# MOTHER_BOARD_SCHEMATIC.net
KiCad netlist of a schematic drawn in EasyEDA
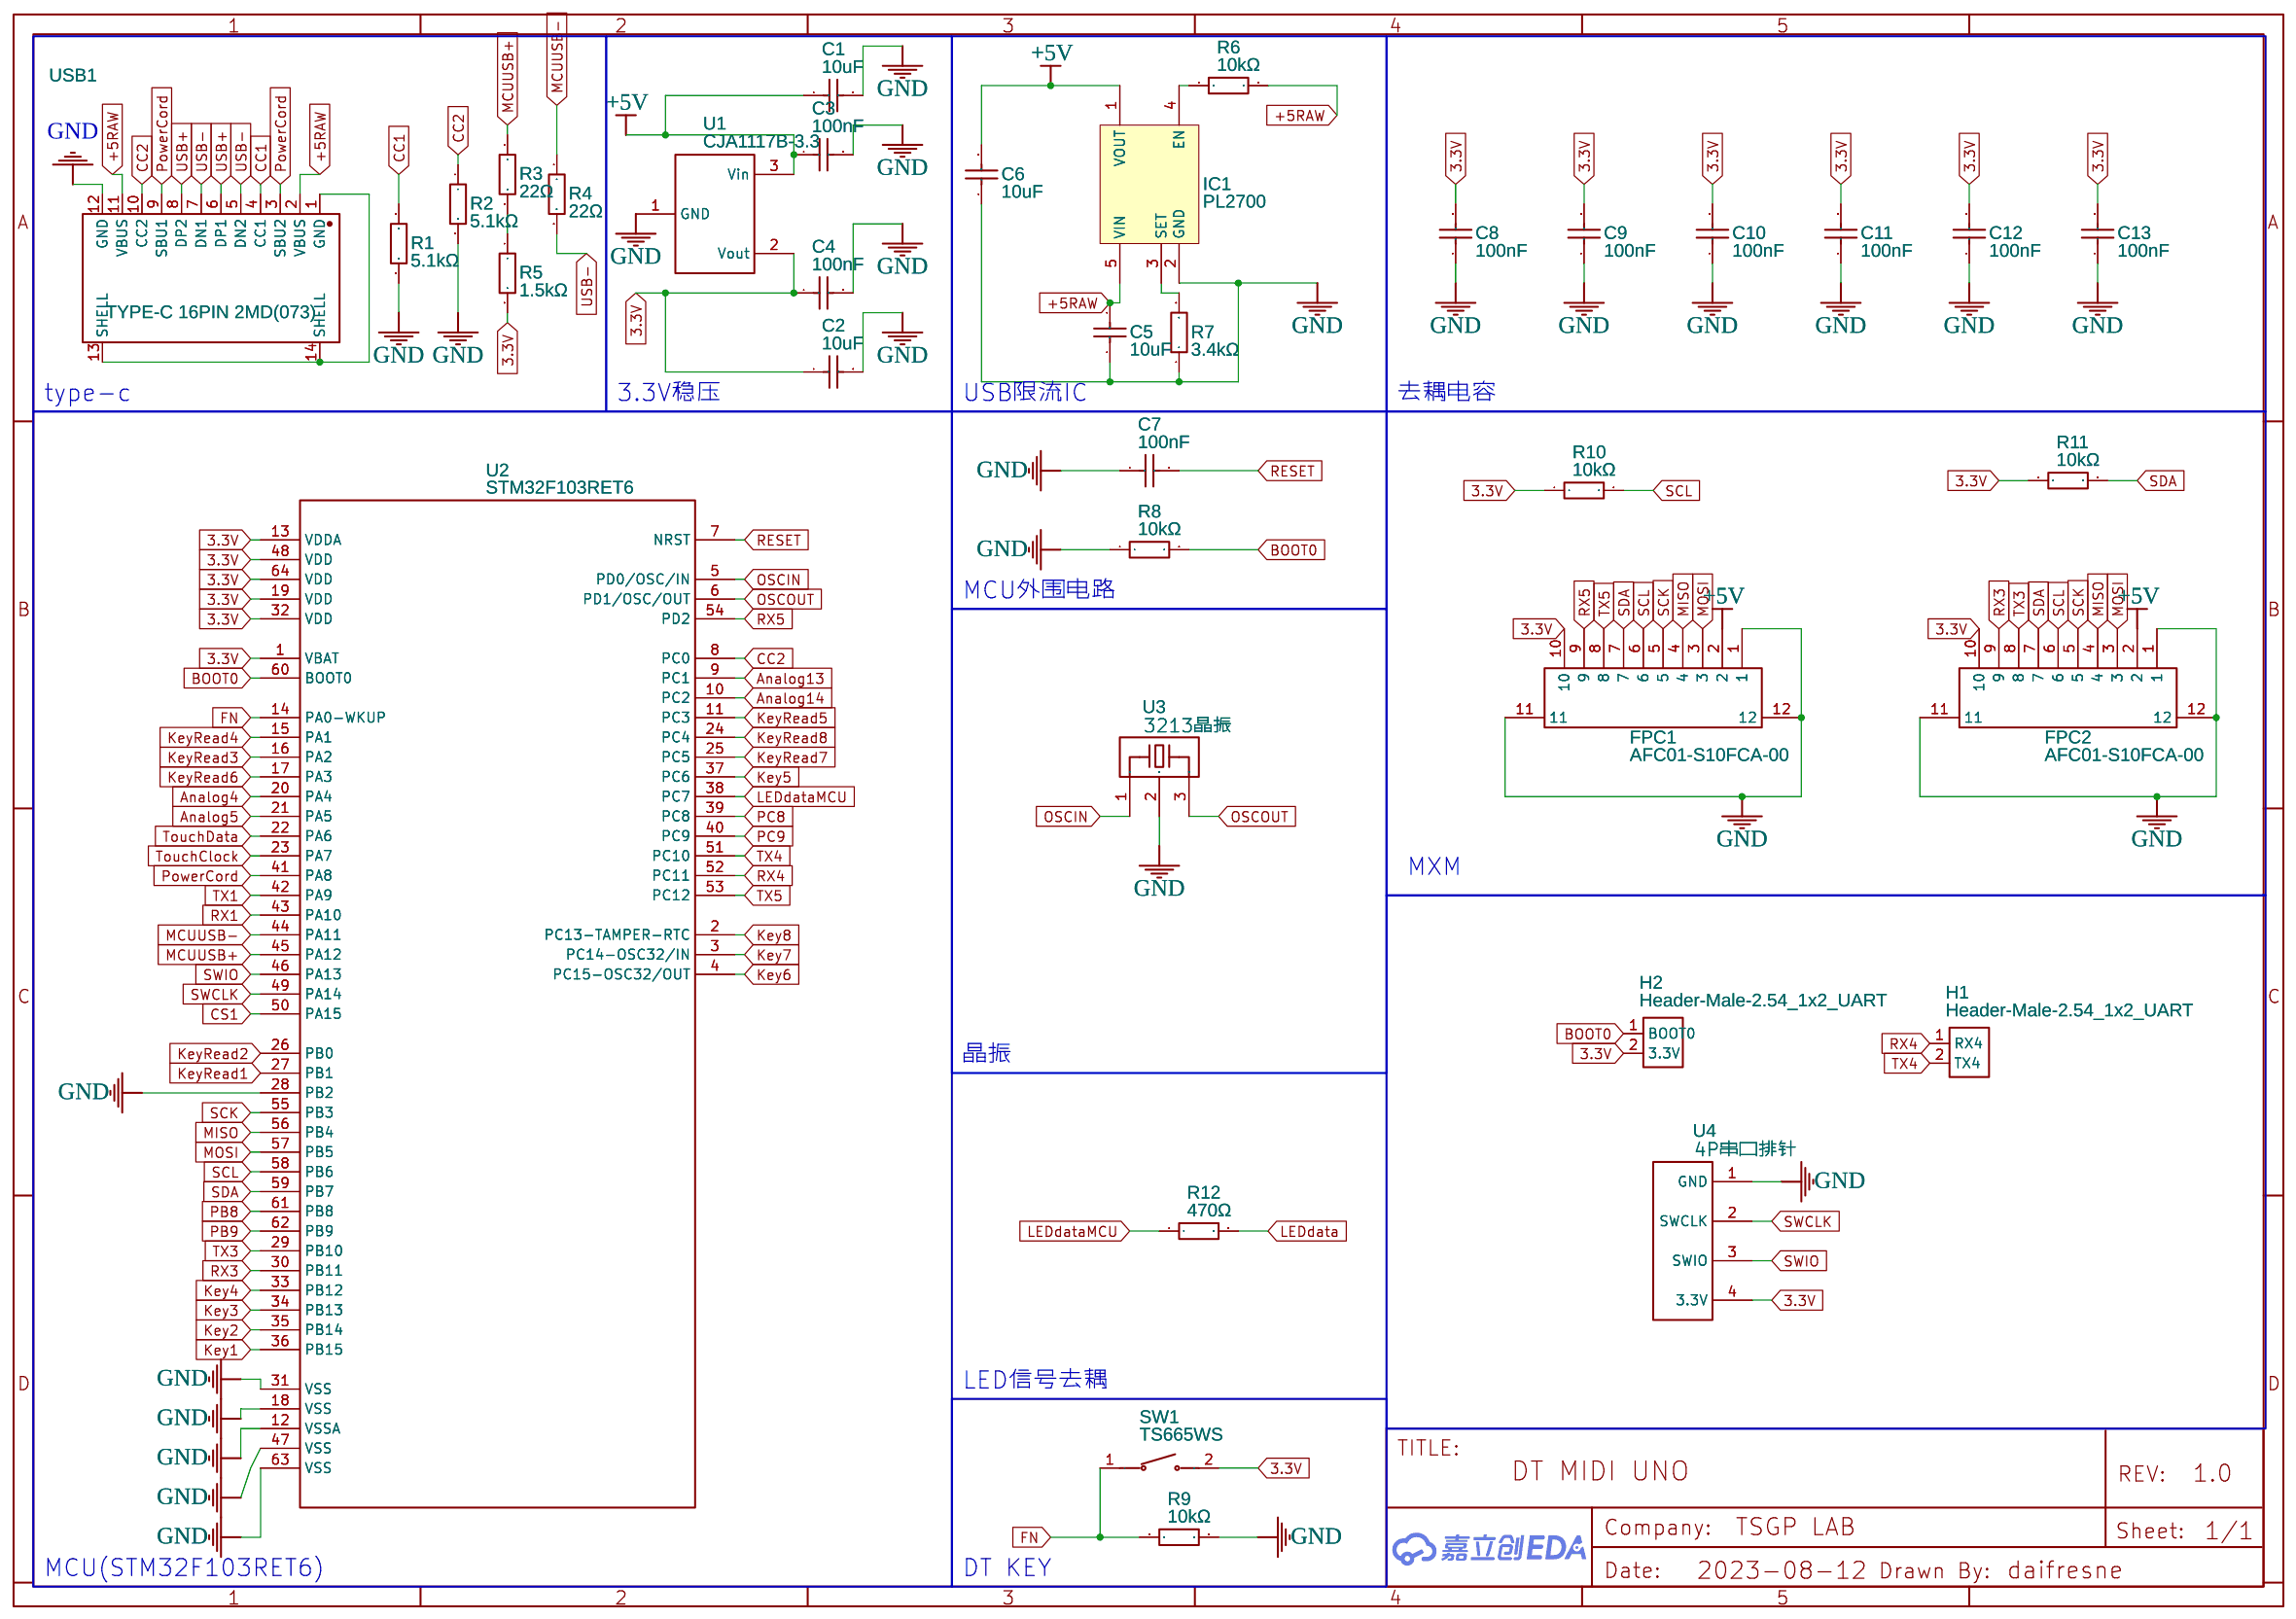
[diagram p0: schematic sheet]

(export (version "E")
  (design (tool "Eeschema 10.0.6"))
  (components
    (comp (ref "C1")
      (value "10uF")
      (fields (field (name "Manufacturer") "SAMSUNG(三星)"))
      (libsource (lib "") (part "CL21A106KAYNNNE"))
    )
    (comp (ref "C2")
      (value "10uF")
      (fields (field (name "Manufacturer") "SAMSUNG(三星)"))
      (libsource (lib "") (part "CL21A106KAYNNNE"))
    )
    (comp (ref "C3")
      (value "100nF")
      (fields (field (name "Manufacturer") "YAGEO(国巨)"))
      (libsource (lib "") (part "CC0603KRX7R8BB104_1"))
    )
    (comp (ref "C4")
      (value "100nF")
      (fields (field (name "Manufacturer") "YAGEO(国巨)"))
      (libsource (lib "") (part "CC0603KRX7R8BB104_1"))
    )
    (comp (ref "C5")
      (value "10uF")
      (fields (field (name "Manufacturer") "SAMSUNG(三星)"))
      (libsource (lib "") (part "CL21A106KAYNNNE_1"))
    )
    (comp (ref "C6")
      (value "10uF")
      (fields (field (name "Manufacturer") "SAMSUNG(三星)"))
      (libsource (lib "") (part "CL21A106KAYNNNE_1"))
    )
    (comp (ref "C7")
      (value "100nF")
      (fields (field (name "Manufacturer") "YAGEO(国巨)"))
      (libsource (lib "") (part "CC0603KRX7R8BB104_1"))
    )
    (comp (ref "C8")
      (value "100nF")
      (fields (field (name "Manufacturer") "YAGEO(国巨)"))
      (libsource (lib "") (part "CC0603KRX7R8BB104"))
    )
    (comp (ref "C9")
      (value "100nF")
      (fields (field (name "Manufacturer") "YAGEO(国巨)"))
      (libsource (lib "") (part "CC0603KRX7R8BB104"))
    )
    (comp (ref "C10")
      (value "100nF")
      (fields (field (name "Manufacturer") "YAGEO(国巨)"))
      (libsource (lib "") (part "CC0603KRX7R8BB104"))
    )
    (comp (ref "C11")
      (value "100nF")
      (fields (field (name "Manufacturer") "YAGEO(国巨)"))
      (libsource (lib "") (part "CC0603KRX7R8BB104"))
    )
    (comp (ref "C12")
      (value "100nF")
      (fields (field (name "Manufacturer") "YAGEO(国巨)"))
      (libsource (lib "") (part "CC0603KRX7R8BB104"))
    )
    (comp (ref "C13")
      (value "100nF")
      (fields (field (name "Manufacturer") "YAGEO(国巨)"))
      (libsource (lib "") (part "CC0603KRX7R8BB104"))
    )
    (comp (ref "FPC1")
      (value "AFC01-S10FCA-00")
      (fields (field (name "Manufacturer") "JS(钜硕电子)"))
      (libsource (lib "") (part "AFC01-S10FCA-00"))
    )
    (comp (ref "FPC2")
      (value "AFC01-S10FCA-00")
      (fields (field (name "Manufacturer") "JS(钜硕电子)"))
      (libsource (lib "") (part "AFC01-S10FCA-00"))
    )
    (comp (ref "H1")
      (value "Header-Male-2.54_1x2_UART")
      (fields (field (name "Manufacturer Part") "826629-2") (field (name "Manufacturer") "TE Connectivity"))
      (libsource (lib "") (part "Header-Male-2.54_1x2_UART_1"))
    )
    (comp (ref "H2")
      (value "Header-Male-2.54_1x2_UART")
      (fields (field (name "Manufacturer Part") "826629-2") (field (name "Manufacturer") "TE Connectivity"))
      (libsource (lib "") (part "Header-Male-2.54_1x2_UART"))
    )
    (comp (ref "IC1") (value "PL2700") (libsource (lib "") (part "PL2700")))
    (comp (ref "R1")
      (value "5.1kΩ")
      (fields (field (name "Manufacturer") "YAGEO(国巨)"))
      (libsource (lib "") (part "RT0603BRD075K1L_1"))
    )
    (comp (ref "R2")
      (value "5.1kΩ")
      (fields (field (name "Manufacturer") "YAGEO(国巨)"))
      (libsource (lib "") (part "RT0603BRD075K1L"))
    )
    (comp (ref "R3")
      (value "22Ω")
      (fields (field (name "Manufacturer") "UNI-ROYAL(厚声)"))
      (libsource (lib "") (part "0603WAF220JT5E"))
    )
    (comp (ref "R4")
      (value "22Ω")
      (fields (field (name "Manufacturer") "UNI-ROYAL(厚声)"))
      (libsource (lib "") (part "0603WAF220JT5E"))
    )
    (comp (ref "R5")
      (value "1.5kΩ")
      (fields (field (name "Manufacturer") "UNI-ROYAL(厚声)"))
      (libsource (lib "") (part "0603WAF1501T5E"))
    )
    (comp (ref "R6")
      (value "10kΩ")
      (fields (field (name "Manufacturer") "YAGEO(国巨)"))
      (libsource (lib "") (part "RT0805BRD0710KL"))
    )
    (comp (ref "R7")
      (value "3.4kΩ")
      (fields (field (name "Manufacturer") "UNI-ROYAL(厚声)"))
      (libsource (lib "") (part "0603WAF3401T5E"))
    )
    (comp (ref "R8")
      (value "10kΩ")
      (fields (field (name "Manufacturer") "YAGEO(国巨)"))
      (libsource (lib "") (part "RT0805BRD0710KL"))
    )
    (comp (ref "R9")
      (value "10kΩ")
      (fields (field (name "Manufacturer") "YAGEO(国巨)"))
      (libsource (lib "") (part "RT0805BRD0710KL"))
    )
    (comp (ref "R10")
      (value "10kΩ")
      (fields (field (name "Manufacturer") "YAGEO(国巨)"))
      (libsource (lib "") (part "RT0805BRD0710KL"))
    )
    (comp (ref "R11")
      (value "10kΩ")
      (fields (field (name "Manufacturer") "YAGEO(国巨)"))
      (libsource (lib "") (part "RT0805BRD0710KL"))
    )
    (comp (ref "R12")
      (value "470Ω")
      (fields (field (name "Manufacturer") "UNI-ROYAL(厚声)"))
      (libsource (lib "") (part "0603WAF4700T5E"))
    )
    (comp (ref "SW1")
      (value "TS665WS")
      (fields (field (name "Manufacturer") "SHOU HAN(首韩)"))
      (libsource (lib "") (part "TS665WS"))
    )
    (comp (ref "U1")
      (value "CJA1117B-3.3")
      (fields (field (name "Manufacturer") "CJ(江苏长电/长晶)"))
      (libsource (lib "") (part "CJA1117B-3.3"))
    )
    (comp (ref "U2")
      (value "STM32F103RET6")
      (fields (field (name "Manufacturer") "ST(意法半导体)"))
      (libsource (lib "") (part "STM32F103RET6"))
    )
    (comp (ref "U3") (value "3213晶振") (libsource (lib "") (part "3213晶振")))
    (comp (ref "U4") (value "4P串口排针") (libsource (lib "") (part "4P串口排针")))
    (comp (ref "USB1")
      (value "TYPE-C 16PIN 2MD(073)")
      (fields (field (name "Manufacturer") "SHOU HAN(首韩)"))
      (libsource (lib "") (part "TYPE-C 16PIN 2MD(073)"))
    )
  )
  (nets
    (net (code "1") (name "+5RAW") (class "Default")
      (node (ref "C5") (pin "2") (pinfunction "2_2") (pintype "input"))
      (node (ref "IC1") (pin "5") (pinfunction "VIN_5") (pintype "unspecified"))
      (node (ref "R6") (pin "2") (pinfunction "2_2") (pintype "input"))
      (node (ref "USB1") (pin "11") (pinfunction "VBUS_11") (pintype "unspecified"))
      (node (ref "USB1") (pin "2") (pinfunction "VBUS_2") (pintype "unspecified"))
    )
    (net (code "2") (name "+5V") (class "Default")
      (node (ref "C1") (pin "1") (pinfunction "1_1") (pintype "input"))
      (node (ref "C3") (pin "1") (pinfunction "1_1") (pintype "input"))
      (node (ref "C6") (pin "2") (pinfunction "2_2") (pintype "input"))
      (node (ref "FPC1") (pin "2") (pinfunction "2_2") (pintype "unspecified"))
      (node (ref "FPC2") (pin "2") (pinfunction "2_2") (pintype "unspecified"))
      (node (ref "IC1") (pin "1") (pinfunction "VOUT_1") (pintype "unspecified"))
      (node (ref "U1") (pin "3") (pinfunction "Vin_3") (pintype "unspecified"))
    )
    (net (code "3") (name "3.3V") (class "Default")
      (node (ref "C10") (pin "2") (pinfunction "2_2") (pintype "input"))
      (node (ref "C11") (pin "2") (pinfunction "2_2") (pintype "input"))
      (node (ref "C12") (pin "2") (pinfunction "2_2") (pintype "input"))
      (node (ref "C13") (pin "2") (pinfunction "2_2") (pintype "input"))
      (node (ref "C2") (pin "1") (pinfunction "1_1") (pintype "input"))
      (node (ref "C4") (pin "1") (pinfunction "1_1") (pintype "input"))
      (node (ref "C8") (pin "2") (pinfunction "2_2") (pintype "input"))
      (node (ref "C9") (pin "2") (pinfunction "2_2") (pintype "input"))
      (node (ref "FPC1") (pin "10") (pinfunction "10_10") (pintype "unspecified"))
      (node (ref "FPC2") (pin "10") (pinfunction "10_10") (pintype "unspecified"))
      (node (ref "H2") (pin "2") (pinfunction "3.3V_2") (pintype "unspecified"))
      (node (ref "R10") (pin "1") (pinfunction "1_1") (pintype "input"))
      (node (ref "R11") (pin "1") (pinfunction "1_1") (pintype "input"))
      (node (ref "R5") (pin "2") (pinfunction "2_2") (pintype "input"))
      (node (ref "SW1") (pin "2") (pinfunction "B_2") (pintype "unspecified"))
      (node (ref "U1") (pin "2") (pinfunction "Vout_2") (pintype "unspecified"))
      (node (ref "U2") (pin "1") (pinfunction "VBAT_1") (pintype "input"))
      (node (ref "U2") (pin "13") (pinfunction "VDDA_13") (pintype "passive"))
      (node (ref "U2") (pin "19") (pinfunction "VDD_19") (pintype "passive"))
      (node (ref "U2") (pin "32") (pinfunction "VDD_32") (pintype "passive"))
      (node (ref "U2") (pin "48") (pinfunction "VDD_48") (pintype "passive"))
      (node (ref "U2") (pin "64") (pinfunction "VDD_64") (pintype "passive"))
      (node (ref "U4") (pin "4") (pinfunction "3.3V_4") (pintype "unspecified"))
    )
    (net (code "4") (name "Analog4") (class "Default")
      (node (ref "U2") (pin "20") (pinfunction "PA4_20") (pintype "unspecified"))
    )
    (net (code "5") (name "Analog5") (class "Default")
      (node (ref "U2") (pin "21") (pinfunction "PA5_21") (pintype "unspecified"))
    )
    (net (code "6") (name "Analog13") (class "Default")
      (node (ref "U2") (pin "9") (pinfunction "PC1_9") (pintype "unspecified"))
    )
    (net (code "7") (name "Analog14") (class "Default")
      (node (ref "U2") (pin "10") (pinfunction "PC2_10") (pintype "unspecified"))
    )
    (net (code "8") (name "BOOT0") (class "Default")
      (node (ref "H2") (pin "1") (pinfunction "BOOT0_1") (pintype "unspecified"))
      (node (ref "R8") (pin "2") (pinfunction "2_2") (pintype "input"))
      (node (ref "U2") (pin "60") (pinfunction "BOOT0_60") (pintype "unspecified"))
    )
    (net (code "9") (name "CC1") (class "Default")
      (node (ref "R1") (pin "2") (pinfunction "2_2") (pintype "input"))
      (node (ref "USB1") (pin "4") (pinfunction "CC1_4") (pintype "unspecified"))
    )
    (net (code "10") (name "CC2") (class "Default")
      (node (ref "R2") (pin "1") (pinfunction "1_1") (pintype "input"))
      (node (ref "U2") (pin "8") (pinfunction "PC0_8") (pintype "unspecified"))
      (node (ref "USB1") (pin "10") (pinfunction "CC2_10") (pintype "unspecified"))
    )
    (net (code "11") (name "CS1") (class "Default")
      (node (ref "U2") (pin "50") (pinfunction "PA15_50") (pintype "unspecified"))
    )
    (net (code "12") (name "FN") (class "Default")
      (node (ref "R9") (pin "1") (pinfunction "1_1") (pintype "input"))
      (node (ref "SW1") (pin "1") (pinfunction "A_1") (pintype "unspecified"))
      (node (ref "U2") (pin "14") (pinfunction "PA0-WKUP_14") (pintype "unspecified"))
    )
    (net (code "13") (name "GND") (class "Default")
      (node (ref "C1") (pin "2") (pinfunction "2_2") (pintype "input"))
      (node (ref "C10") (pin "1") (pinfunction "1_1") (pintype "input"))
      (node (ref "C11") (pin "1") (pinfunction "1_1") (pintype "input"))
      (node (ref "C12") (pin "1") (pinfunction "1_1") (pintype "input"))
      (node (ref "C13") (pin "1") (pinfunction "1_1") (pintype "input"))
      (node (ref "C2") (pin "2") (pinfunction "2_2") (pintype "input"))
      (node (ref "C3") (pin "2") (pinfunction "2_2") (pintype "input"))
      (node (ref "C4") (pin "2") (pinfunction "2_2") (pintype "input"))
      (node (ref "C5") (pin "1") (pinfunction "1_1") (pintype "input"))
      (node (ref "C6") (pin "1") (pinfunction "1_1") (pintype "input"))
      (node (ref "C7") (pin "1") (pinfunction "1_1") (pintype "input"))
      (node (ref "C8") (pin "1") (pinfunction "1_1") (pintype "input"))
      (node (ref "C9") (pin "1") (pinfunction "1_1") (pintype "input"))
      (node (ref "FPC1") (pin "1") (pinfunction "1_1") (pintype "unspecified"))
      (node (ref "FPC1") (pin "11") (pinfunction "11_11") (pintype "unspecified"))
      (node (ref "FPC1") (pin "12") (pinfunction "12_12") (pintype "unspecified"))
      (node (ref "FPC2") (pin "1") (pinfunction "1_1") (pintype "unspecified"))
      (node (ref "FPC2") (pin "11") (pinfunction "11_11") (pintype "unspecified"))
      (node (ref "FPC2") (pin "12") (pinfunction "12_12") (pintype "unspecified"))
      (node (ref "IC1") (pin "2") (pinfunction "GND_2") (pintype "unspecified"))
      (node (ref "R1") (pin "1") (pinfunction "1_1") (pintype "input"))
      (node (ref "R2") (pin "2") (pinfunction "2_2") (pintype "input"))
      (node (ref "R7") (pin "1") (pinfunction "1_1") (pintype "input"))
      (node (ref "R8") (pin "1") (pinfunction "1_1") (pintype "input"))
      (node (ref "R9") (pin "2") (pinfunction "2_2") (pintype "input"))
      (node (ref "U1") (pin "1") (pinfunction "GND_1") (pintype "unspecified"))
      (node (ref "U2") (pin "12") (pinfunction "VSSA_12") (pintype "unspecified"))
      (node (ref "U2") (pin "18") (pinfunction "VSS_18") (pintype "unspecified"))
      (node (ref "U2") (pin "28") (pinfunction "PB2_28") (pintype "unspecified"))
      (node (ref "U2") (pin "31") (pinfunction "VSS_31") (pintype "unspecified"))
      (node (ref "U2") (pin "47") (pinfunction "VSS_47") (pintype "unspecified"))
      (node (ref "U2") (pin "63") (pinfunction "VSS_63") (pintype "unspecified"))
      (node (ref "U3") (pin "2") (pinfunction "2_2") (pintype "unspecified"))
      (node (ref "U4") (pin "1") (pinfunction "GND_1") (pintype "unspecified"))
      (node (ref "USB1") (pin "12") (pinfunction "GND_12") (pintype "unspecified"))
    )
    (net (code "14") (name "Key1") (class "Default")
      (node (ref "U2") (pin "36") (pinfunction "PB15_36") (pintype "unspecified"))
    )
    (net (code "15") (name "Key2") (class "Default")
      (node (ref "U2") (pin "35") (pinfunction "PB14_35") (pintype "unspecified"))
    )
    (net (code "16") (name "Key3") (class "Default")
      (node (ref "U2") (pin "34") (pinfunction "PB13_34") (pintype "unspecified"))
    )
    (net (code "17") (name "Key4") (class "Default")
      (node (ref "U2") (pin "33") (pinfunction "PB12_33") (pintype "unspecified"))
    )
    (net (code "18") (name "Key5") (class "Default")
      (node (ref "U2") (pin "37") (pinfunction "PC6_37") (pintype "unspecified"))
    )
    (net (code "19") (name "Key6") (class "Default")
      (node (ref "U2") (pin "4") (pinfunction "PC15-OSC32/OUT_4") (pintype "output"))
    )
    (net (code "20") (name "Key7") (class "Default")
      (node (ref "U2") (pin "3") (pinfunction "PC14-OSC32/IN_3") (pintype "input"))
    )
    (net (code "21") (name "Key8") (class "Default")
      (node (ref "U2") (pin "2") (pinfunction "PC13-TAMPER-RTC_2") (pintype "input"))
    )
    (net (code "22") (name "KeyRead1") (class "Default")
      (node (ref "U2") (pin "27") (pinfunction "PB1_27") (pintype "unspecified"))
    )
    (net (code "23") (name "KeyRead2") (class "Default")
      (node (ref "U2") (pin "26") (pinfunction "PB0_26") (pintype "unspecified"))
    )
    (net (code "24") (name "KeyRead3") (class "Default")
      (node (ref "U2") (pin "16") (pinfunction "PA2_16") (pintype "unspecified"))
    )
    (net (code "25") (name "KeyRead4") (class "Default")
      (node (ref "U2") (pin "15") (pinfunction "PA1_15") (pintype "unspecified"))
    )
    (net (code "26") (name "KeyRead5") (class "Default")
      (node (ref "U2") (pin "11") (pinfunction "PC3_11") (pintype "unspecified"))
    )
    (net (code "27") (name "KeyRead6") (class "Default")
      (node (ref "U2") (pin "17") (pinfunction "PA3_17") (pintype "unspecified"))
    )
    (net (code "28") (name "KeyRead7") (class "Default")
      (node (ref "U2") (pin "25") (pinfunction "PC5_25") (pintype "unspecified"))
    )
    (net (code "29") (name "KeyRead8") (class "Default")
      (node (ref "U2") (pin "24") (pinfunction "PC4_24") (pintype "unspecified"))
    )
    (net (code "30") (name "LEDdata") (class "Default")
      (node (ref "R12") (pin "2") (pinfunction "2_2") (pintype "input"))
    )
    (net (code "31") (name "LEDdataMCU") (class "Default")
      (node (ref "R12") (pin "1") (pinfunction "1_1") (pintype "input"))
      (node (ref "U2") (pin "38") (pinfunction "PC7_38") (pintype "unspecified"))
    )
    (net (code "32") (name "MCUUSB+") (class "Default")
      (node (ref "R3") (pin "1") (pinfunction "1_1") (pintype "input"))
      (node (ref "U2") (pin "45") (pinfunction "PA12_45") (pintype "unspecified"))
    )
    (net (code "33") (name "MCUUSB-") (class "Default")
      (node (ref "R4") (pin "1") (pinfunction "1_1") (pintype "input"))
      (node (ref "U2") (pin "44") (pinfunction "PA11_44") (pintype "unspecified"))
    )
    (net (code "34") (name "MISO") (class "Default")
      (node (ref "FPC1") (pin "4") (pinfunction "4_4") (pintype "unspecified"))
      (node (ref "FPC2") (pin "4") (pinfunction "4_4") (pintype "unspecified"))
      (node (ref "U2") (pin "56") (pinfunction "PB4_56") (pintype "unspecified"))
    )
    (net (code "35") (name "MOSI") (class "Default")
      (node (ref "FPC1") (pin "3") (pinfunction "3_3") (pintype "unspecified"))
      (node (ref "FPC2") (pin "3") (pinfunction "3_3") (pintype "unspecified"))
      (node (ref "U2") (pin "57") (pinfunction "PB5_57") (pintype "unspecified"))
    )
    (net (code "36") (name "Net-(IC1-EN)") (class "Default")
      (node (ref "IC1") (pin "4") (pinfunction "EN_4") (pintype "unspecified"))
      (node (ref "R6") (pin "1") (pinfunction "1_1") (pintype "input"))
    )
    (net (code "37") (name "Net-(IC1-SET)") (class "Default")
      (node (ref "IC1") (pin "3") (pinfunction "SET_3") (pintype "unspecified"))
      (node (ref "R7") (pin "2") (pinfunction "2_2") (pintype "input"))
    )
    (net (code "38") (name "Net-(R3-Pad2)") (class "Default")
      (node (ref "R3") (pin "2") (pinfunction "2_2") (pintype "input"))
      (node (ref "R5") (pin "1") (pinfunction "1_1") (pintype "input"))
    )
    (net (code "39") (name "Net-(USB1-GND-Pad1)") (class "Default")
      (node (ref "USB1") (pin "1") (pinfunction "GND_1") (pintype "unspecified"))
      (node (ref "USB1") (pin "13") (pinfunction "SHELL_13") (pintype "unspecified"))
      (node (ref "USB1") (pin "14") (pinfunction "SHELL_14") (pintype "unspecified"))
    )
    (net (code "40") (name "OSCIN") (class "Default")
      (node (ref "U2") (pin "5") (pinfunction "PD0/OSC/IN_5") (pintype "input"))
      (node (ref "U3") (pin "1") (pinfunction "1_1") (pintype "unspecified"))
    )
    (net (code "41") (name "OSCOUT") (class "Default")
      (node (ref "U2") (pin "6") (pinfunction "PD1/OSC/OUT_6") (pintype "output"))
      (node (ref "U3") (pin "3") (pinfunction "3_3") (pintype "unspecified"))
    )
    (net (code "42") (name "PB8") (class "Default")
      (node (ref "U2") (pin "61") (pinfunction "PB8_61") (pintype "unspecified"))
    )
    (net (code "43") (name "PB9") (class "Default")
      (node (ref "U2") (pin "62") (pinfunction "PB9_62") (pintype "unspecified"))
    )
    (net (code "44") (name "PC8") (class "Default")
      (node (ref "U2") (pin "39") (pinfunction "PC8_39") (pintype "unspecified"))
    )
    (net (code "45") (name "PC9") (class "Default")
      (node (ref "U2") (pin "40") (pinfunction "PC9_40") (pintype "unspecified"))
    )
    (net (code "46") (name "PowerCord") (class "Default")
      (node (ref "U2") (pin "41") (pinfunction "PA8_41") (pintype "unspecified"))
      (node (ref "USB1") (pin "3") (pinfunction "SBU2_3") (pintype "unspecified"))
      (node (ref "USB1") (pin "9") (pinfunction "SBU1_9") (pintype "unspecified"))
    )
    (net (code "47") (name "RESET") (class "Default")
      (node (ref "C7") (pin "2") (pinfunction "2_2") (pintype "input"))
      (node (ref "U2") (pin "7") (pinfunction "NRST_7") (pintype "output"))
    )
    (net (code "48") (name "RX1") (class "Default")
      (node (ref "U2") (pin "43") (pinfunction "PA10_43") (pintype "unspecified"))
    )
    (net (code "49") (name "RX3") (class "Default")
      (node (ref "FPC2") (pin "9") (pinfunction "9_9") (pintype "unspecified"))
      (node (ref "U2") (pin "30") (pinfunction "PB11_30") (pintype "unspecified"))
    )
    (net (code "50") (name "RX4") (class "Default")
      (node (ref "H1") (pin "1") (pinfunction "RX4_1") (pintype "unspecified"))
      (node (ref "U2") (pin "52") (pinfunction "PC11_52") (pintype "unspecified"))
    )
    (net (code "51") (name "RX5") (class "Default")
      (node (ref "FPC1") (pin "9") (pinfunction "9_9") (pintype "unspecified"))
      (node (ref "U2") (pin "54") (pinfunction "PD2_54") (pintype "unspecified"))
    )
    (net (code "52") (name "SCK") (class "Default")
      (node (ref "FPC1") (pin "5") (pinfunction "5_5") (pintype "unspecified"))
      (node (ref "FPC2") (pin "5") (pinfunction "5_5") (pintype "unspecified"))
      (node (ref "U2") (pin "55") (pinfunction "PB3_55") (pintype "unspecified"))
    )
    (net (code "53") (name "SCL") (class "Default")
      (node (ref "FPC1") (pin "6") (pinfunction "6_6") (pintype "unspecified"))
      (node (ref "FPC2") (pin "6") (pinfunction "6_6") (pintype "unspecified"))
      (node (ref "R10") (pin "2") (pinfunction "2_2") (pintype "input"))
      (node (ref "U2") (pin "58") (pinfunction "PB6_58") (pintype "unspecified"))
    )
    (net (code "54") (name "SDA") (class "Default")
      (node (ref "FPC1") (pin "7") (pinfunction "7_7") (pintype "unspecified"))
      (node (ref "FPC2") (pin "7") (pinfunction "7_7") (pintype "unspecified"))
      (node (ref "R11") (pin "2") (pinfunction "2_2") (pintype "input"))
      (node (ref "U2") (pin "59") (pinfunction "PB7_59") (pintype "passive"))
    )
    (net (code "55") (name "SWCLK") (class "Default")
      (node (ref "U2") (pin "49") (pinfunction "PA14_49") (pintype "unspecified"))
      (node (ref "U4") (pin "2") (pinfunction "SWCLK_2") (pintype "unspecified"))
    )
    (net (code "56") (name "SWIO") (class "Default")
      (node (ref "U2") (pin "46") (pinfunction "PA13_46") (pintype "unspecified"))
      (node (ref "U4") (pin "3") (pinfunction "SWIO_3") (pintype "unspecified"))
    )
    (net (code "57") (name "TX1") (class "Default")
      (node (ref "U2") (pin "42") (pinfunction "PA9_42") (pintype "unspecified"))
    )
    (net (code "58") (name "TX3") (class "Default")
      (node (ref "FPC2") (pin "8") (pinfunction "8_8") (pintype "unspecified"))
      (node (ref "U2") (pin "29") (pinfunction "PB10_29") (pintype "unspecified"))
    )
    (net (code "59") (name "TX4") (class "Default")
      (node (ref "H1") (pin "2") (pinfunction "TX4_2") (pintype "unspecified"))
      (node (ref "U2") (pin "51") (pinfunction "PC10_51") (pintype "unspecified"))
    )
    (net (code "60") (name "TX5") (class "Default")
      (node (ref "FPC1") (pin "8") (pinfunction "8_8") (pintype "unspecified"))
      (node (ref "U2") (pin "53") (pinfunction "PC12_53") (pintype "unspecified"))
    )
    (net (code "61") (name "TouchClock") (class "Default")
      (node (ref "U2") (pin "23") (pinfunction "PA7_23") (pintype "passive"))
    )
    (net (code "62") (name "TouchData") (class "Default")
      (node (ref "U2") (pin "22") (pinfunction "PA6_22") (pintype "unspecified"))
    )
    (net (code "63") (name "USB+") (class "Default")
      (node (ref "USB1") (pin "6") (pinfunction "DP1_6") (pintype "unspecified"))
      (node (ref "USB1") (pin "8") (pinfunction "DP2_8") (pintype "unspecified"))
    )
    (net (code "64") (name "USB-") (class "Default")
      (node (ref "R4") (pin "2") (pinfunction "2_2") (pintype "input"))
      (node (ref "USB1") (pin "5") (pinfunction "DN2_5") (pintype "unspecified"))
      (node (ref "USB1") (pin "7") (pinfunction "DN1_7") (pintype "unspecified"))
    )
  )
)
